# connect.net
KiCad netlist of a schematic drawn in Altium Designer
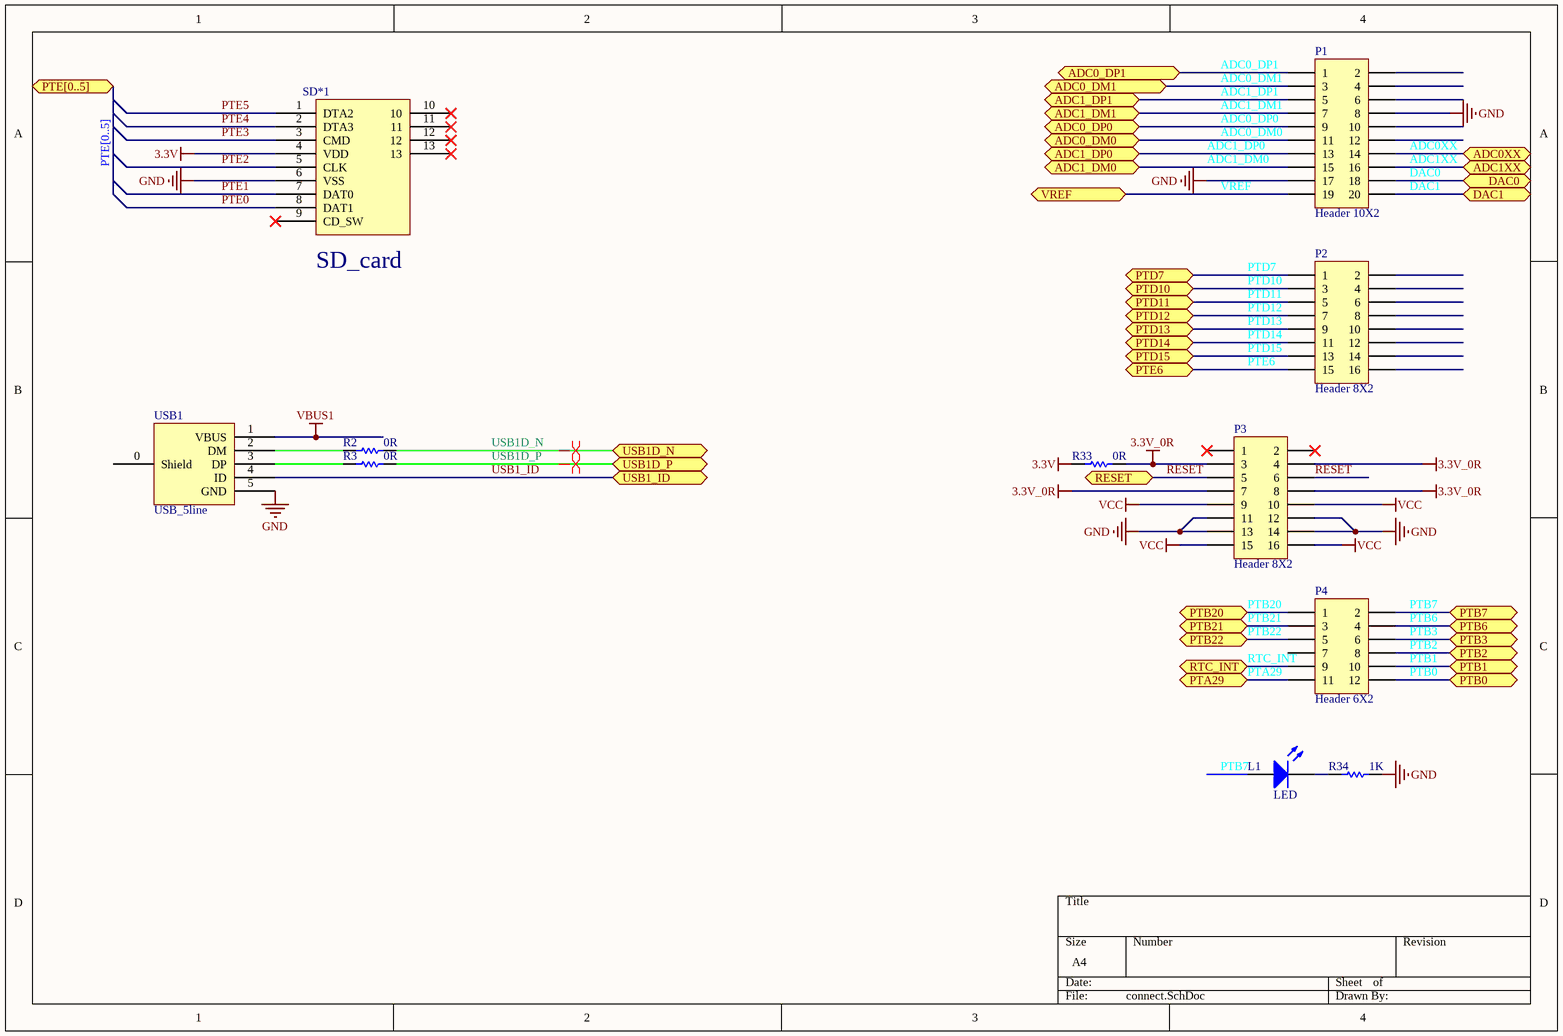
[diagram p0: connect.SchDoc]

(export (version "E")
  (design (tool "Eeschema 10.0.6"))
  (components
    (comp (ref "L1") (value "LED") (footprint "1608[0603]") (libsource (lib "Sparks") (part "LED")))
    (comp (ref "P1")
      (value "Header 10X2")
      (footprint "HDR2X10")
      (description "Header, 10-Pin, Dual row")
      (fields (field (name "PUBLISHER") "Altium Limited"))
      (libsource (lib "Sparks") (part "Header 10X2"))
    )
    (comp (ref "P2")
      (value "Header 8X2")
      (footprint "HDR2X8")
      (description "Header, 8-Pin, Dual row")
      (fields (field (name "PUBLISHER") "Altium Limited"))
      (libsource (lib "Sparks") (part "Header 8X2"))
    )
    (comp (ref "P3")
      (value "Header 8X2")
      (footprint "HDR2X8")
      (description "Header, 8-Pin, Dual row")
      (fields (field (name "PUBLISHER") "Altium Limited"))
      (libsource (lib "Sparks") (part "Header 8X2"))
    )
    (comp (ref "P4")
      (value "Header 6X2")
      (footprint "HDR2X6")
      (description "Header, 6-Pin, Dual row")
      (fields (field (name "PUBLISHER") "Altium Limited"))
      (libsource (lib "Sparks") (part "Header 6X2"))
    )
    (comp (ref "R2")
      (value "0R")
      (footprint "1608[0603]")
      (description "贴片电阻")
      (fields (field (name "Comment") "Res") (field (name "PUBLISHER") "Altium Limited"))
      (libsource (lib "Sparks") (part "Res"))
    )
    (comp (ref "R3")
      (value "0R")
      (footprint "1608[0603]")
      (description "贴片电阻")
      (fields (field (name "Comment") "Res") (field (name "PUBLISHER") "Altium Limited"))
      (libsource (lib "Sparks") (part "Res"))
    )
    (comp (ref "R33")
      (value "0R")
      (footprint "1206")
      (description "贴片电阻")
      (fields (field (name "Comment") "Res") (field (name "PUBLISHER") "Altium Limited"))
      (libsource (lib "Sparks") (part "Res"))
    )
    (comp (ref "R34")
      (value "1K")
      (footprint "1608[0603]")
      (description "贴片电阻")
      (fields (field (name "Comment") "Res") (field (name "PUBLISHER") "Altium Limited"))
      (libsource (lib "Sparks") (part "Res"))
    )
    (comp (ref "SD*1") (value "TF_card") (footprint "TF卡座(短体)") (libsource (lib "2号库") (part "TF_card")))
    (comp (ref "USB1")
      (value "USB_5line")
      (footprint "USB-MICRO-5P-2F")
      (libsource (lib "2号库") (part "USB_5line"))
    )
  )
  (nets
    (net (code "1") (name "/ADC0XX") (class "Default")
      (node (ref "P1") (pin "14") (pinfunction "14_14") (pintype "passive"))
    )
    (net (code "2") (name "/ADC0_DM0") (class "Default")
      (node (ref "P1") (pin "11") (pinfunction "11_11") (pintype "passive"))
    )
    (net (code "3") (name "/ADC0_DM1") (class "Default")
      (node (ref "P1") (pin "3") (pinfunction "3_3") (pintype "passive"))
    )
    (net (code "4") (name "/ADC0_DP0") (class "Default")
      (node (ref "P1") (pin "9") (pinfunction "9_9") (pintype "passive"))
    )
    (net (code "5") (name "/ADC0_DP1") (class "Default")
      (node (ref "P1") (pin "1") (pinfunction "1_1") (pintype "passive"))
    )
    (net (code "6") (name "/ADC1XX") (class "Default")
      (node (ref "P1") (pin "16") (pinfunction "16_16") (pintype "passive"))
    )
    (net (code "7") (name "/ADC1_DM0") (class "Default")
      (node (ref "P1") (pin "15") (pinfunction "15_15") (pintype "passive"))
    )
    (net (code "8") (name "/ADC1_DM1") (class "Default")
      (node (ref "P1") (pin "7") (pinfunction "7_7") (pintype "passive"))
    )
    (net (code "9") (name "/ADC1_DP0") (class "Default")
      (node (ref "P1") (pin "13") (pinfunction "13_13") (pintype "passive"))
    )
    (net (code "10") (name "/ADC1_DP1") (class "Default")
      (node (ref "P1") (pin "5") (pinfunction "5_5") (pintype "passive"))
    )
    (net (code "11") (name "/DAC0") (class "Default")
      (node (ref "P1") (pin "18") (pinfunction "18_18") (pintype "passive"))
    )
    (net (code "12") (name "/DAC1") (class "Default")
      (node (ref "P1") (pin "20") (pinfunction "20_20") (pintype "passive"))
    )
    (net (code "13") (name "/PTA29") (class "Default")
      (node (ref "P4") (pin "11") (pinfunction "11_11") (pintype "passive"))
    )
    (net (code "14") (name "/PTB0") (class "Default")
      (node (ref "P4") (pin "12") (pinfunction "12_12") (pintype "passive"))
    )
    (net (code "15") (name "/PTB1") (class "Default")
      (node (ref "P4") (pin "10") (pinfunction "10_10") (pintype "passive"))
    )
    (net (code "16") (name "/PTB2") (class "Default")
      (node (ref "P4") (pin "8") (pinfunction "8_8") (pintype "passive"))
    )
    (net (code "17") (name "/PTB3") (class "Default")
      (node (ref "P4") (pin "6") (pinfunction "6_6") (pintype "passive"))
    )
    (net (code "18") (name "/PTB6") (class "Default")
      (node (ref "P4") (pin "4") (pinfunction "4_4") (pintype "passive"))
    )
    (net (code "19") (name "/PTB7") (class "Default")
      (node (ref "L1") (pin "1") (pinfunction "A_1") (pintype "passive"))
      (node (ref "P4") (pin "2") (pinfunction "2_2") (pintype "passive"))
    )
    (net (code "20") (name "/PTB20") (class "Default")
      (node (ref "P4") (pin "1") (pinfunction "1_1") (pintype "passive"))
    )
    (net (code "21") (name "/PTB21") (class "Default")
      (node (ref "P4") (pin "3") (pinfunction "3_3") (pintype "passive"))
    )
    (net (code "22") (name "/PTB22") (class "Default")
      (node (ref "P4") (pin "5") (pinfunction "5_5") (pintype "passive"))
    )
    (net (code "23") (name "/PTD7") (class "Default")
      (node (ref "P2") (pin "1") (pinfunction "1_1") (pintype "passive"))
    )
    (net (code "24") (name "/PTD10") (class "Default")
      (node (ref "P2") (pin "3") (pinfunction "3_3") (pintype "passive"))
    )
    (net (code "25") (name "/PTD11") (class "Default")
      (node (ref "P2") (pin "5") (pinfunction "5_5") (pintype "passive"))
    )
    (net (code "26") (name "/PTD12") (class "Default")
      (node (ref "P2") (pin "7") (pinfunction "7_7") (pintype "passive"))
    )
    (net (code "27") (name "/PTD13") (class "Default")
      (node (ref "P2") (pin "9") (pinfunction "9_9") (pintype "passive"))
    )
    (net (code "28") (name "/PTD14") (class "Default")
      (node (ref "P2") (pin "11") (pinfunction "11_11") (pintype "passive"))
    )
    (net (code "29") (name "/PTD15") (class "Default")
      (node (ref "P2") (pin "13") (pinfunction "13_13") (pintype "passive"))
    )
    (net (code "30") (name "/PTE0") (class "Default")
      (node (ref "SD*1") (pin "8") (pinfunction "DAT1_8") (pintype "passive"))
    )
    (net (code "31") (name "/PTE1") (class "Default")
      (node (ref "SD*1") (pin "7") (pinfunction "DAT0_7") (pintype "passive"))
    )
    (net (code "32") (name "/PTE2") (class "Default")
      (node (ref "SD*1") (pin "5") (pinfunction "CLK_5") (pintype "passive"))
    )
    (net (code "33") (name "/PTE3") (class "Default")
      (node (ref "SD*1") (pin "3") (pinfunction "CMD_3") (pintype "passive"))
    )
    (net (code "34") (name "/PTE4") (class "Default")
      (node (ref "SD*1") (pin "2") (pinfunction "DTA3_2") (pintype "passive"))
    )
    (net (code "35") (name "/PTE5") (class "Default")
      (node (ref "SD*1") (pin "1") (pinfunction "DTA2_1") (pintype "passive"))
    )
    (net (code "36") (name "/PTE6") (class "Default")
      (node (ref "P2") (pin "15") (pinfunction "15_15") (pintype "passive"))
    )
    (net (code "38") (name "/RESET") (class "Default")
      (node (ref "P3") (pin "5") (pinfunction "5_5") (pintype "passive"))
      (node (ref "P3") (pin "6") (pinfunction "6_6") (pintype "passive"))
    )
    (net (code "39") (name "/RTC_INT") (class "Default")
      (node (ref "P4") (pin "9") (pinfunction "9_9") (pintype "passive"))
    )
    (net (code "40") (name "/USB1D_N") (class "Default")
      (node (ref "R2") (pin "1") (pinfunction "1_1") (pintype "passive"))
    )
    (net (code "41") (name "/USB1D_P") (class "Default")
      (node (ref "R3") (pin "1") (pinfunction "1_1") (pintype "passive"))
    )
    (net (code "42") (name "/USB1_ID") (class "Default")
      (node (ref "USB1") (pin "4") (pinfunction "ID_4") (pintype "passive"))
    )
    (net (code "43") (name "/VREF") (class "Default")
      (node (ref "P1") (pin "19") (pinfunction "19_19") (pintype "passive"))
    )
    (net (code "44") (name "3.3V") (class "Default")
      (node (ref "R33") (pin "2") (pinfunction "2_2") (pintype "passive"))
      (node (ref "SD*1") (pin "4") (pinfunction "VDD_4") (pintype "passive"))
    )
    (net (code "45") (name "3.3V_0R") (class "Default")
      (node (ref "P3") (pin "3") (pinfunction "3_3") (pintype "passive"))
      (node (ref "P3") (pin "4") (pinfunction "4_4") (pintype "passive"))
      (node (ref "P3") (pin "7") (pinfunction "7_7") (pintype "passive"))
      (node (ref "P3") (pin "8") (pinfunction "8_8") (pintype "passive"))
      (node (ref "R33") (pin "1") (pinfunction "1_1") (pintype "passive"))
    )
    (net (code "46") (name "GND") (class "Default")
      (node (ref "P1") (pin "17") (pinfunction "17_17") (pintype "passive"))
      (node (ref "P1") (pin "8") (pinfunction "8_8") (pintype "passive"))
      (node (ref "P3") (pin "11") (pinfunction "11_11") (pintype "passive"))
      (node (ref "P3") (pin "12") (pinfunction "12_12") (pintype "passive"))
      (node (ref "P3") (pin "13") (pinfunction "13_13") (pintype "passive"))
      (node (ref "P3") (pin "14") (pinfunction "14_14") (pintype "passive"))
      (node (ref "R34") (pin "1") (pinfunction "1_1") (pintype "passive"))
      (node (ref "SD*1") (pin "6") (pinfunction "VSS_6") (pintype "passive"))
      (node (ref "USB1") (pin "5") (pinfunction "GND_5") (pintype "passive"))
    )
    (net (code "47") (name "Net-(L1-K)") (class "Default")
      (node (ref "L1") (pin "2") (pinfunction "K_2") (pintype "passive"))
      (node (ref "R34") (pin "2") (pinfunction "2_2") (pintype "passive"))
    )
    (net (code "48") (name "Net-(USB1-DM)") (class "Default")
      (node (ref "R2") (pin "2") (pinfunction "2_2") (pintype "passive"))
      (node (ref "USB1") (pin "2") (pinfunction "DM_2") (pintype "passive"))
    )
    (net (code "49") (name "Net-(USB1-DP)") (class "Default")
      (node (ref "R3") (pin "2") (pinfunction "2_2") (pintype "passive"))
      (node (ref "USB1") (pin "3") (pinfunction "DP_3") (pintype "passive"))
    )
    (net (code "50") (name "VBUS1") (class "Default")
      (node (ref "USB1") (pin "1") (pinfunction "VBUS_1") (pintype "passive"))
    )
    (net (code "51") (name "VCC") (class "Default")
      (node (ref "P3") (pin "10") (pinfunction "10_10") (pintype "passive"))
      (node (ref "P3") (pin "15") (pinfunction "15_15") (pintype "passive"))
      (node (ref "P3") (pin "16") (pinfunction "16_16") (pintype "passive"))
      (node (ref "P3") (pin "9") (pinfunction "9_9") (pintype "passive"))
    )
    (net (code "52") (name "unconnected-(P1-Pad2)") (class "Default")
      (node (ref "P1") (pin "2") (pinfunction "2_2") (pintype "passive"))
    )
    (net (code "53") (name "unconnected-(P1-Pad4)") (class "Default")
      (node (ref "P1") (pin "4") (pinfunction "4_4") (pintype "passive"))
    )
    (net (code "54") (name "unconnected-(P1-Pad6)") (class "Default")
      (node (ref "P1") (pin "6") (pinfunction "6_6") (pintype "passive"))
    )
    (net (code "55") (name "unconnected-(P1-Pad10)") (class "Default")
      (node (ref "P1") (pin "10") (pinfunction "10_10") (pintype "passive"))
    )
    (net (code "56") (name "unconnected-(P1-Pad12)") (class "Default")
      (node (ref "P1") (pin "12") (pinfunction "12_12") (pintype "passive"))
    )
    (net (code "57") (name "unconnected-(P2-Pad2)") (class "Default")
      (node (ref "P2") (pin "2") (pinfunction "2_2") (pintype "passive"))
    )
    (net (code "58") (name "unconnected-(P2-Pad4)") (class "Default")
      (node (ref "P2") (pin "4") (pinfunction "4_4") (pintype "passive"))
    )
    (net (code "59") (name "unconnected-(P2-Pad6)") (class "Default")
      (node (ref "P2") (pin "6") (pinfunction "6_6") (pintype "passive"))
    )
    (net (code "60") (name "unconnected-(P2-Pad8)") (class "Default")
      (node (ref "P2") (pin "8") (pinfunction "8_8") (pintype "passive"))
    )
    (net (code "61") (name "unconnected-(P2-Pad10)") (class "Default")
      (node (ref "P2") (pin "10") (pinfunction "10_10") (pintype "passive"))
    )
    (net (code "62") (name "unconnected-(P2-Pad12)") (class "Default")
      (node (ref "P2") (pin "12") (pinfunction "12_12") (pintype "passive"))
    )
    (net (code "63") (name "unconnected-(P2-Pad14)") (class "Default")
      (node (ref "P2") (pin "14") (pinfunction "14_14") (pintype "passive"))
    )
    (net (code "64") (name "unconnected-(P2-Pad16)") (class "Default")
      (node (ref "P2") (pin "16") (pinfunction "16_16") (pintype "passive"))
    )
    (net (code "65") (name "unconnected-(P3-Pad1)") (class "Default")
      (node (ref "P3") (pin "1") (pinfunction "1_1") (pintype "passive+no_connect"))
    )
    (net (code "66") (name "unconnected-(P3-Pad2)") (class "Default")
      (node (ref "P3") (pin "2") (pinfunction "2_2") (pintype "passive+no_connect"))
    )
    (net (code "67") (name "unconnected-(P4-Pad7)") (class "Default")
      (node (ref "P4") (pin "7") (pinfunction "7_7") (pintype "passive"))
    )
    (net (code "68") (name "unconnected-(SD*1-CD_SW-Pad9)") (class "Default")
      (node (ref "SD*1") (pin "9") (pinfunction "CD_SW_9") (pintype "passive+no_connect"))
    )
    (net (code "69") (name "unconnected-(SD*1-Pad10)") (class "Default")
      (node (ref "SD*1") (pin "10") (pinfunction "10_10") (pintype "passive+no_connect"))
    )
    (net (code "70") (name "unconnected-(SD*1-Pad11)") (class "Default")
      (node (ref "SD*1") (pin "11") (pinfunction "11_11") (pintype "passive+no_connect"))
    )
    (net (code "71") (name "unconnected-(SD*1-Pad12)") (class "Default")
      (node (ref "SD*1") (pin "12") (pinfunction "12_12") (pintype "passive+no_connect"))
    )
    (net (code "72") (name "unconnected-(SD*1-Pad13)") (class "Default")
      (node (ref "SD*1") (pin "13") (pinfunction "13_13") (pintype "passive+no_connect"))
    )
    (net (code "73") (name "unconnected-(USB1-Shield-Pad0)") (class "Default")
      (node (ref "USB1") (pin "0") (pinfunction "Shield_0") (pintype "passive"))
    )
  )
)
